# CH32F203VCT6-R1.net
KiCad netlist of a schematic drawn in Altium Designer
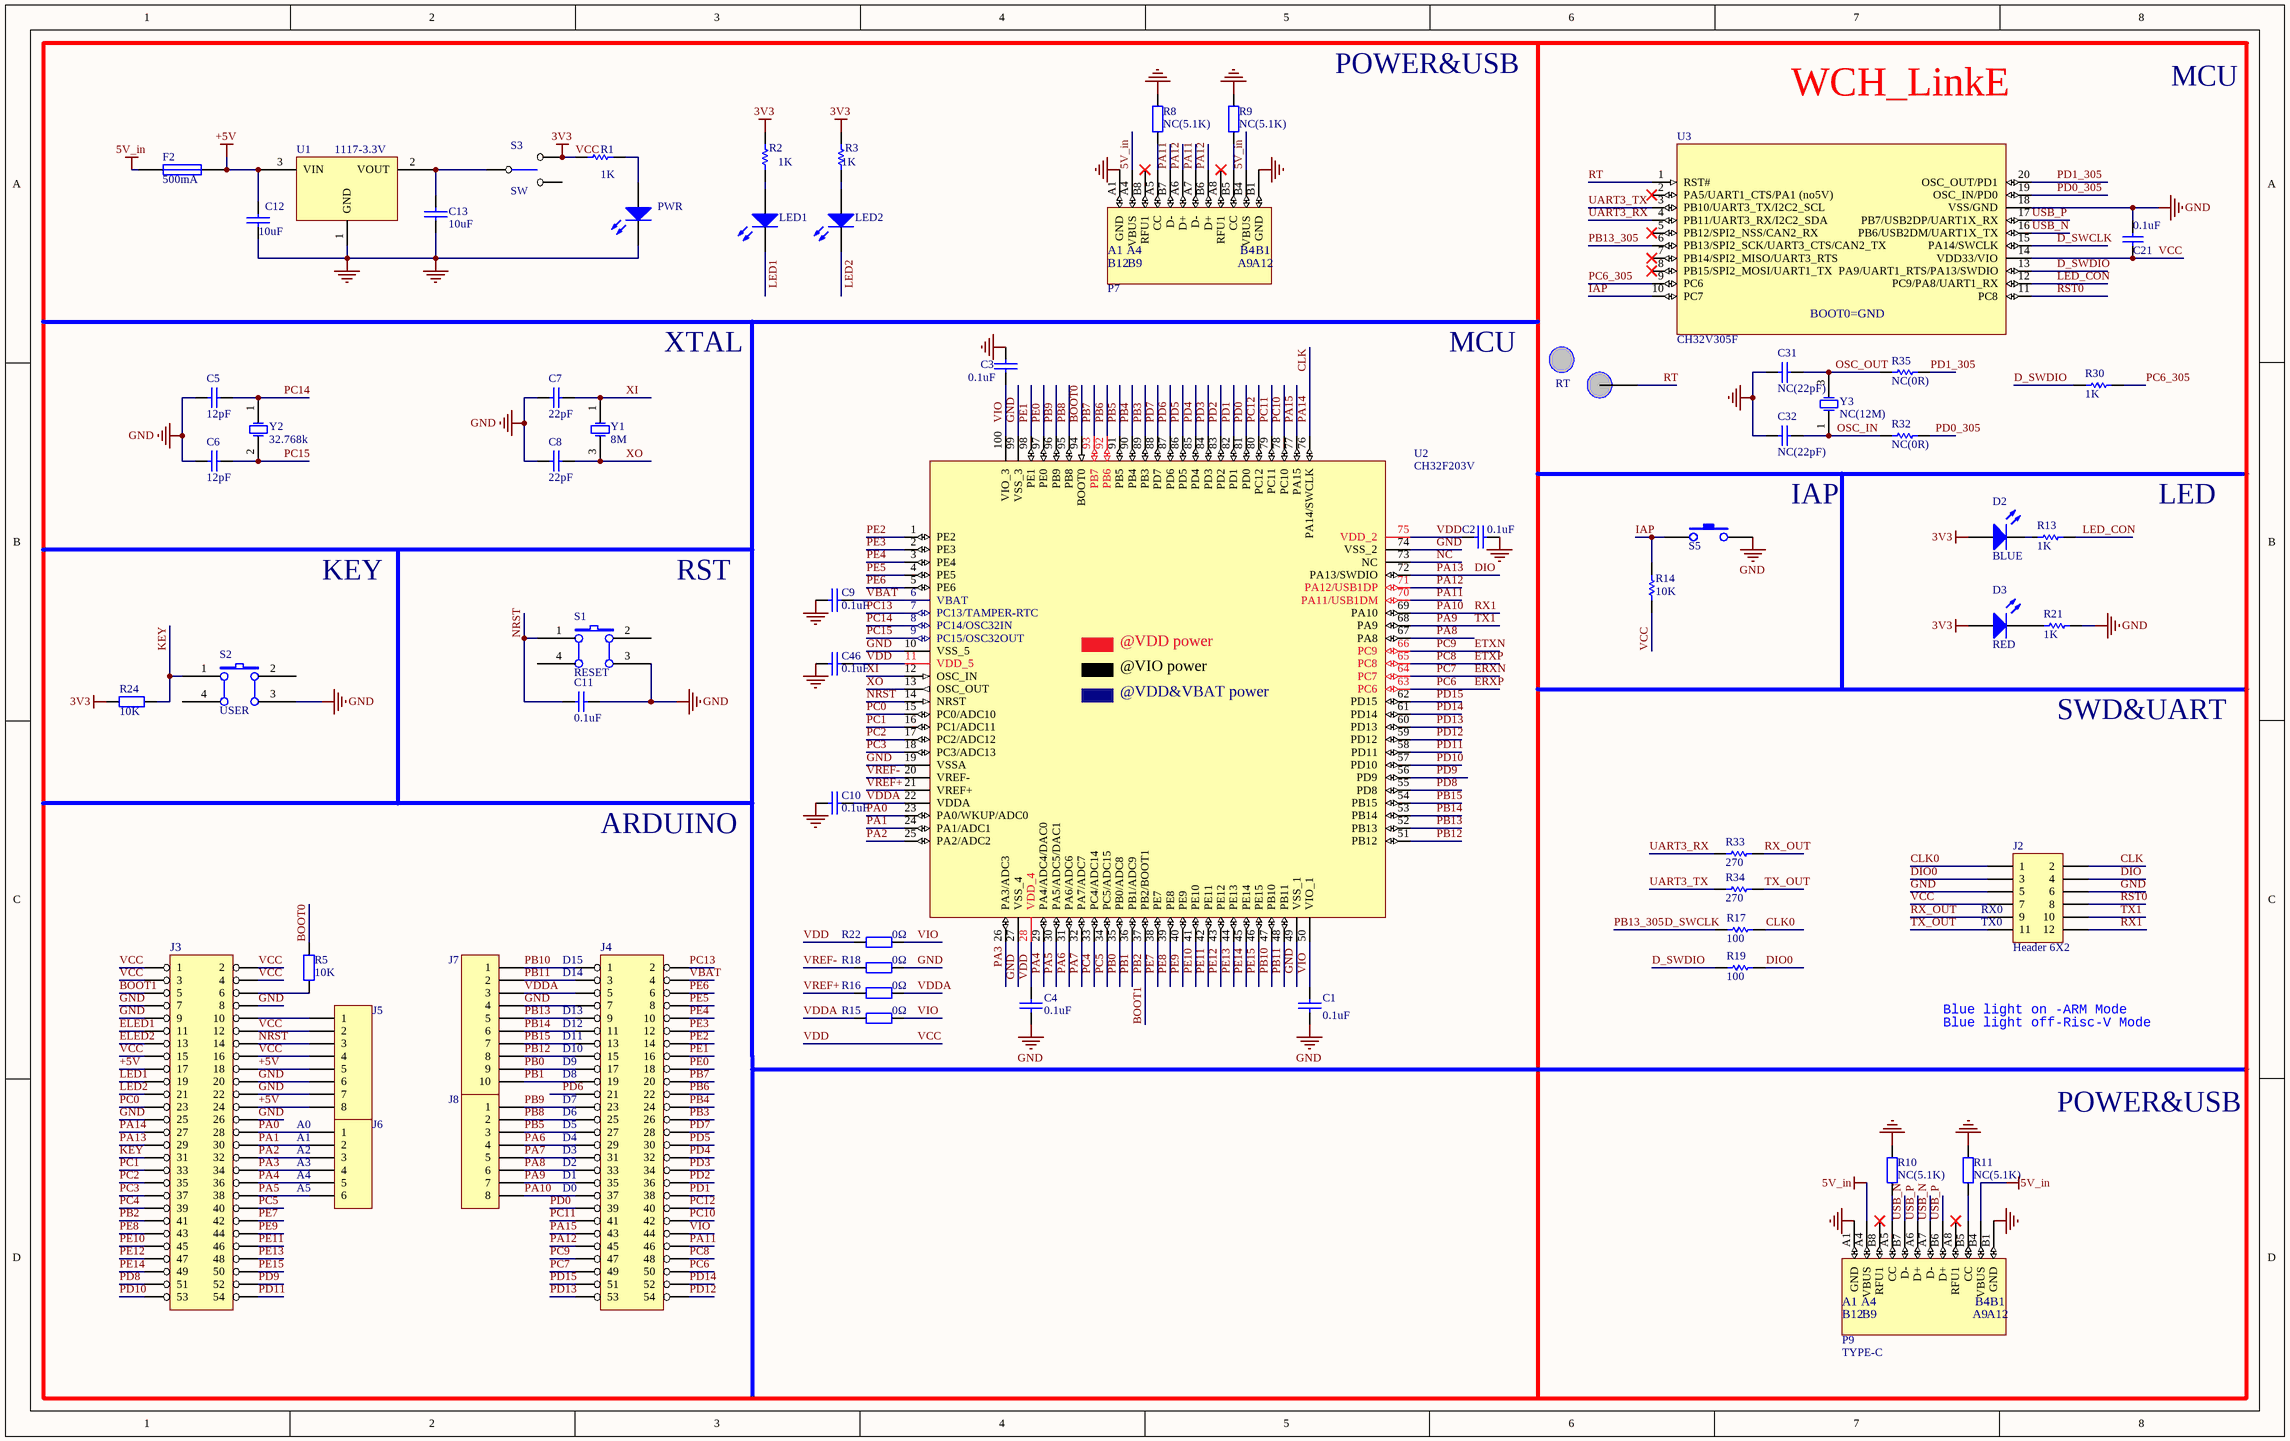
[diagram p0: CH32F203VCT6-R1.SchDoc]

(export (version "E")
  (design (tool "Eeschema 10.0.6"))
  (components
    (comp (ref "C1")
      (value "0.1uF")
      (footprint "0603_C")
      (description "Capacitor")
      (libsource (lib "*") (part "CAP"))
    )
    (comp (ref "C2")
      (value "0.1uF")
      (footprint "0603_C")
      (description "Capacitor")
      (libsource (lib "*") (part "CAP"))
    )
    (comp (ref "C3")
      (value "0.1uF")
      (footprint "0603_C")
      (description "Capacitor")
      (libsource (lib "*") (part "CAP"))
    )
    (comp (ref "C4")
      (value "0.1uF")
      (footprint "0603_C")
      (description "Capacitor")
      (libsource (lib "*") (part "CAP"))
    )
    (comp (ref "C5")
      (value "12pF")
      (footprint "0603_C")
      (description "Capacitor")
      (libsource (lib "Miscellaneous Devices") (part "Cap"))
    )
    (comp (ref "C6")
      (value "12pF")
      (footprint "0603_C")
      (description "Capacitor")
      (libsource (lib "Miscellaneous Devices") (part "Cap"))
    )
    (comp (ref "C7")
      (value "22pF")
      (footprint "0603_C")
      (description "Capacitor")
      (libsource (lib "Miscellaneous Devices") (part "Cap"))
    )
    (comp (ref "C8")
      (value "22pF")
      (footprint "0603_C")
      (description "Capacitor")
      (libsource (lib "Miscellaneous Devices") (part "Cap"))
    )
    (comp (ref "C9")
      (value "0.1uF")
      (footprint "0603_C")
      (description "Capacitor")
      (libsource (lib "*") (part "CAP"))
    )
    (comp (ref "C10")
      (value "0.1uF")
      (footprint "0603_C")
      (description "Capacitor")
      (libsource (lib "*") (part "CAP"))
    )
    (comp (ref "C11")
      (value "0.1uF")
      (footprint "0603_C")
      (description "Capacitor")
      (libsource (lib "Miscellaneous Devices") (part "Cap"))
    )
    (comp (ref "C12")
      (value "10uF")
      (footprint "3216_C")
      (description "Capacitor")
      (libsource (lib "*") (part "CAP"))
    )
    (comp (ref "C13")
      (value "10uF")
      (footprint "3216_C")
      (description "Capacitor")
      (libsource (lib "*") (part "CAP"))
    )
    (comp (ref "C21")
      (value "0.1uF")
      (footprint "0603_C")
      (description "Capacitor")
      (libsource (lib "Miscellaneous Devices") (part "Cap"))
    )
    (comp (ref "C31")
      (value "NC(22pF)")
      (footprint "0603_C")
      (description "Capacitor")
      (fields (field (name "PUBLISHER") "Altium Limited"))
      (libsource (lib "*") (part "Cap"))
    )
    (comp (ref "C32")
      (value "NC(22pF)")
      (footprint "0603_C")
      (description "Capacitor")
      (fields (field (name "PUBLISHER") "Altium Limited"))
      (libsource (lib "*") (part "Cap"))
    )
    (comp (ref "C46")
      (value "0.1uF")
      (footprint "0603_C")
      (description "Capacitor")
      (libsource (lib "*") (part "CAP"))
    )
    (comp (ref "D2")
      (value "BLUE")
      (footprint "0603+")
      (description "Typical RED, GREEN, YELLOW, AMBER GaAs LED")
      (fields (field (name "PUBLISHER") "Altium Limited"))
      (libsource (lib "MYLIB") (part "D0603"))
    )
    (comp (ref "D3")
      (value "RED")
      (footprint "0603+")
      (description "Typical RED, GREEN, YELLOW, AMBER GaAs LED")
      (fields (field (name "PUBLISHER") "Altium Limited"))
      (libsource (lib "MYLIB") (part "D0603"))
    )
    (comp (ref "F2")
      (value "500mA")
      (footprint "0805")
      (description "Fuse")
      (libsource (lib "*") (part "FUSE1"))
    )
    (comp (ref "J2")
      (value "Header 6X2")
      (footprint "IDC12-2.54mm")
      (description "Header, 6-Pin, Dual row")
      (fields (field (name "PUBLISHER") "Altium Limited"))
      (libsource (lib "Miscellaneous Connectors") (part "Header 6X2"))
    )
    (comp (ref "J3")
      (value "HEADER 27x2")
      (footprint "MYPCB:IDC54-2.54MM")
      (description "Header, 27-Pin, Dual row")
      (libsource (lib "wch_sch_others") (part "HEADER 27x2"))
    )
    (comp (ref "J4")
      (value "HEADER 27x2")
      (footprint "MYPCB:IDC54-2.54MM")
      (description "Header, 27-Pin, Dual row")
      (libsource (lib "wch_sch_others") (part "HEADER 27x2"))
    )
    (comp (ref "J5")
      (value "Header 8")
      (footprint "SIP8-2.54mm")
      (description "Header, 8-Pin")
      (fields (field (name "PUBLISHER") "Altium Limited"))
      (libsource (lib "") (part "Header 8_1"))
    )
    (comp (ref "J6")
      (value "Header 6")
      (footprint "SIP6-2.54MM")
      (description "Header, 6-Pin")
      (fields (field (name "PUBLISHER") "Altium Limited"))
      (libsource (lib "Miscellaneous Connectors") (part "Header 6"))
    )
    (comp (ref "J7")
      (value "Header 10")
      (footprint "SIP10-2.54mm")
      (description "Header, 10-Pin")
      (fields (field (name "PUBLISHER") "Altium Limited"))
      (libsource (lib "Miscellaneous Connectors") (part "Header 10"))
    )
    (comp (ref "J8")
      (value "Header 8")
      (footprint "SIP8-2.54mm")
      (description "Header, 8-Pin")
      (fields (field (name "PUBLISHER") "Altium Limited"))
      (libsource (lib "Miscellaneous Connectors") (part "Header 8"))
    )
    (comp (ref "LED1")
      (value "LED1   blue")
      (footprint "0603+")
      (description "Typical INFRARED GaAs LED")
      (fields (field (name "PUBLISHER") "Altium Limited"))
      (libsource (lib "Miscellaneous Devices") (part "LED0"))
    )
    (comp (ref "LED2")
      (value "LED2  blue")
      (footprint "0603+")
      (description "Typical INFRARED GaAs LED")
      (fields (field (name "PUBLISHER") "Altium Limited"))
      (libsource (lib "Miscellaneous Devices") (part "LED0"))
    )
    (comp (ref "P7")
      (value "USBFS")
      (footprint "TYPE-C-Receptacle-2.0")
      (libsource (lib "*") (part "TYPE-C1"))
    )
    (comp (ref "P9")
      (value "TYPE-C")
      (footprint "TYPE-C-Receptacle-2.0")
      (libsource (lib "*") (part "TYPE-C1"))
    )
    (comp (ref "PWR")
      (value "POWER  red")
      (footprint "0603+")
      (description "Typical INFRARED GaAs LED")
      (fields (field (name "PUBLISHER") "Altium Limited"))
      (libsource (lib "Miscellaneous Devices") (part "LED0"))
    )
    (comp (ref "R1")
      (value "1K")
      (footprint "0603")
      (description "Semiconductor Resistor")
      (libsource (lib "Miscellaneous Devices") (part "Res Semi"))
    )
    (comp (ref "R2")
      (value "1K")
      (footprint "0603")
      (description "Semiconductor Resistor")
      (libsource (lib "Miscellaneous Devices") (part "Res Semi"))
    )
    (comp (ref "R3")
      (value "1K")
      (footprint "0603")
      (description "Semiconductor Resistor")
      (libsource (lib "Miscellaneous Devices") (part "Res Semi"))
    )
    (comp (ref "R5")
      (value "10K")
      (footprint "0603")
      (description "Resistor")
      (libsource (lib "Miscellaneous Devices") (part "Res2"))
    )
    (comp (ref "R8")
      (value "NC(5.1K)")
      (footprint "0603")
      (description "Resistor")
      (libsource (lib "") (part "Res2_2"))
    )
    (comp (ref "R9")
      (value "NC(5.1K)")
      (footprint "0603")
      (description "Resistor")
      (libsource (lib "") (part "Res2_2"))
    )
    (comp (ref "R10")
      (value "NC(5.1K)")
      (footprint "0603")
      (description "Resistor")
      (libsource (lib "Miscellaneous Devices") (part "Res2"))
    )
    (comp (ref "R11")
      (value "NC(5.1K)")
      (footprint "0603")
      (description "Resistor")
      (libsource (lib "Miscellaneous Devices") (part "Res2"))
    )
    (comp (ref "R13")
      (value "1K")
      (footprint "0603")
      (description "Resistor")
      (fields (field (name "PUBLISHER") "Altium Limited"))
      (libsource (lib "MYLIB") (part "0603-1"))
    )
    (comp (ref "R14")
      (value "10K")
      (footprint "0603")
      (description "Resistor")
      (fields (field (name "PUBLISHER") "Altium Limited"))
      (libsource (lib "MYLIB") (part "0603-1"))
    )
    (comp (ref "R15")
      (value "0Ω")
      (footprint "0603")
      (description "Resistor")
      (libsource (lib "") (part "Res2_1"))
    )
    (comp (ref "R16")
      (value "0Ω")
      (footprint "0603")
      (description "Resistor")
      (libsource (lib "") (part "Res2_1"))
    )
    (comp (ref "R17")
      (value "100")
      (footprint "0603")
      (description "Resistor")
      (fields (field (name "PUBLISHER") "Altium Limited"))
      (libsource (lib "MYLIB") (part "0603-1"))
    )
    (comp (ref "R18")
      (value "0Ω")
      (footprint "0603")
      (description "Resistor")
      (libsource (lib "") (part "Res2_1"))
    )
    (comp (ref "R19")
      (value "100")
      (footprint "0603")
      (description "Resistor")
      (fields (field (name "PUBLISHER") "Altium Limited"))
      (libsource (lib "MYLIB") (part "0603-1"))
    )
    (comp (ref "R21")
      (value "1K")
      (footprint "0603")
      (description "Resistor")
      (fields (field (name "PUBLISHER") "Altium Limited"))
      (libsource (lib "MYLIB") (part "0603-1"))
    )
    (comp (ref "R22")
      (value "0Ω")
      (footprint "0603")
      (description "Resistor")
      (libsource (lib "") (part "Res2_1"))
    )
    (comp (ref "R24")
      (value "10K")
      (footprint "0603")
      (description "Resistor")
      (libsource (lib "") (part "Res2_1"))
    )
    (comp (ref "R30")
      (value "1K")
      (footprint "0603")
      (description "Resistor")
      (fields (field (name "PUBLISHER") "Altium Limited"))
      (libsource (lib "MYLIB") (part "0603-1"))
    )
    (comp (ref "R32")
      (value "NC(0R)")
      (footprint "0603")
      (description "Resistor")
      (fields (field (name "PUBLISHER") "Altium Limited"))
      (libsource (lib "MYLIB") (part "0603-1"))
    )
    (comp (ref "R33")
      (value "270")
      (footprint "0603")
      (description "Resistor")
      (fields (field (name "PUBLISHER") "Altium Limited"))
      (libsource (lib "MYLIB") (part "0603-1"))
    )
    (comp (ref "R34")
      (value "270")
      (footprint "0603")
      (description "Resistor")
      (fields (field (name "PUBLISHER") "Altium Limited"))
      (libsource (lib "MYLIB") (part "0603-1"))
    )
    (comp (ref "R35")
      (value "NC(0R)")
      (footprint "0603")
      (description "Resistor")
      (fields (field (name "PUBLISHER") "Altium Limited"))
      (libsource (lib "MYLIB") (part "0603-1"))
    )
    (comp (ref "RT")
      (value "Testpoint")
      (footprint "TESTPOINT1")
      (description "测试点")
      (libsource (lib "wch_sch_others") (part "Testpoint"))
    )
    (comp (ref "S1")
      (value "RESET")
      (footprint "KEYX")
      (description "SE PUSHBUTTON")
      (libsource (lib "Documents") (part "SW PUSHBUTTON"))
    )
    (comp (ref "S2")
      (value "USER")
      (footprint "KEYX")
      (description "SE PUSHBUTTON")
      (libsource (lib "Documents") (part "SW PUSHBUTTON"))
    )
    (comp (ref "S3") (value "SW") (footprint "SW1") (libsource (lib "MYSCH") (part "SW")))
    (comp (ref "S5") (value "KEY") (footprint "贴片按键") (libsource (lib "*") (part "KEY")))
    (comp (ref "U1")
      (value "1117-3.3V")
      (footprint "SOT-223")
      (libsource (lib "wch_sch_others") (part "1117-3.3V"))
    )
    (comp (ref "U2")
      (value "CH32F203V")
      (footprint "LQFP100")
      (description "ARM M3 HD-MCU, 144MHz, 8*UART, 10*Timer, 4*OPA")
      (libsource (lib "CHXXX") (part "CH32F203V"))
    )
    (comp (ref "U3")
      (value "CH32V305F")
      (footprint "TSSOP20")
      (description "RISC-V FPU HD-MCU, 144MHz, USB_480M, CAN, UART*2, SPI")
      (libsource (lib "CHXXX") (part "CH32V305F"))
    )
    (comp (ref "Y1")
      (value "8M")
      (footprint "XT3225")
      (description "Crystal Oscillator")
      (fields (field (name "PUBLISHER") "Altium Limited"))
      (libsource (lib "Miscellaneous Devices") (part "XTAL"))
    )
    (comp (ref "Y2")
      (value "32.768k")
      (footprint "FC-135")
      (description "Crystal Oscillator")
      (fields (field (name "PUBLISHER") "Altium Limited"))
      (libsource (lib "") (part "XTAL_1"))
    )
    (comp (ref "Y3")
      (value "NC(12M)")
      (footprint "XT3225")
      (description "Crystal Oscillator")
      (libsource (lib "*") (part "XTAL"))
    )
  )
  (nets
    (net (code "1") (name "+5V") (class "Default")
      (node (ref "C12") (pin "1") (pinfunction "1_1") (pintype "passive"))
      (node (ref "F2") (pin "2") (pinfunction "2_2") (pintype "passive"))
      (node (ref "J3") (pin "17") (pinfunction "17_17") (pintype "passive"))
      (node (ref "J3") (pin "18") (pinfunction "18_18") (pintype "passive"))
      (node (ref "J3") (pin "24") (pinfunction "24_24") (pintype "passive"))
      (node (ref "J5") (pin "5") (pinfunction "5_5") (pintype "passive"))
      (node (ref "J5") (pin "8") (pinfunction "8_8") (pintype "passive"))
      (node (ref "U1") (pin "3") (pinfunction "VIN_3") (pintype "passive"))
    )
    (net (code "2") (name "/BOOT0") (class "Default")
      (node (ref "R5") (pin "2") (pinfunction "2_2") (pintype "passive"))
      (node (ref "U2") (pin "94") (pinfunction "BOOT0_94") (pintype "input"))
    )
    (net (code "3") (name "/BOOT1") (class "Default")
      (node (ref "J3") (pin "41") (pinfunction "41_41") (pintype "passive"))
      (node (ref "J3") (pin "5") (pinfunction "5_5") (pintype "passive"))
      (node (ref "U2") (pin "37") (pinfunction "PB2/BOOT1_37") (pintype "bidirectional"))
    )
    (net (code "4") (name "/CLK") (class "Default")
      (node (ref "J2") (pin "2") (pinfunction "2_2") (pintype "passive"))
      (node (ref "J3") (pin "27") (pinfunction "27_27") (pintype "passive"))
      (node (ref "U2") (pin "76") (pinfunction "PA14/SWCLK_76") (pintype "bidirectional"))
    )
    (net (code "5") (name "/CLK0") (class "Default")
      (node (ref "J2") (pin "1") (pinfunction "1_1") (pintype "passive"))
      (node (ref "R17") (pin "1") (pinfunction "1_1") (pintype "passive"))
    )
    (net (code "6") (name "/DIO") (class "Default")
      (node (ref "J2") (pin "4") (pinfunction "4_4") (pintype "passive"))
      (node (ref "J3") (pin "29") (pinfunction "29_29") (pintype "passive"))
      (node (ref "U2") (pin "72") (pinfunction "PA13/SWDIO_72") (pintype "bidirectional"))
    )
    (net (code "7") (name "/DIO0") (class "Default")
      (node (ref "J2") (pin "3") (pinfunction "3_3") (pintype "passive"))
      (node (ref "R19") (pin "1") (pinfunction "1_1") (pintype "passive"))
    )
    (net (code "8") (name "/D_SWCLK") (class "Default")
      (node (ref "R17") (pin "2") (pinfunction "2_2") (pintype "passive"))
      (node (ref "U3") (pin "15") (pinfunction "PA14/SWCLK_15") (pintype "bidirectional"))
      (node (ref "U3") (pin "6") (pinfunction "PB13/SPI2_SCK/UART3_CTS/CAN2_TX_6") (pintype "bidirectional"))
    )
    (net (code "9") (name "/D_SWDIO") (class "Default")
      (node (ref "R19") (pin "2") (pinfunction "2_2") (pintype "passive"))
      (node (ref "R30") (pin "1") (pinfunction "1_1") (pintype "passive"))
      (node (ref "U3") (pin "13") (pinfunction "PA9/UART1_RTS/PA13/SWDIO_13") (pintype "bidirectional"))
    )
    (net (code "10") (name "/ELED1") (class "Default")
      (node (ref "J3") (pin "11") (pinfunction "11_11") (pintype "passive"))
    )
    (net (code "11") (name "/ELED2") (class "Default")
      (node (ref "J3") (pin "13") (pinfunction "13_13") (pintype "passive"))
    )
    (net (code "12") (name "/ERXN") (class "Default")
      (node (ref "J4") (pin "49") (pinfunction "49_49") (pintype "passive"))
      (node (ref "U2") (pin "64") (pinfunction "PC7_64") (pintype "bidirectional"))
    )
    (net (code "13") (name "/ERXP") (class "Default")
      (node (ref "J4") (pin "50") (pinfunction "50_50") (pintype "passive"))
      (node (ref "U2") (pin "63") (pinfunction "PC6_63") (pintype "bidirectional"))
    )
    (net (code "14") (name "/ETXN") (class "Default")
      (node (ref "J4") (pin "47") (pinfunction "47_47") (pintype "passive"))
      (node (ref "U2") (pin "66") (pinfunction "PC9_66") (pintype "bidirectional"))
    )
    (net (code "15") (name "/ETXP") (class "Default")
      (node (ref "J4") (pin "48") (pinfunction "48_48") (pintype "passive"))
      (node (ref "U2") (pin "65") (pinfunction "PC8_65") (pintype "bidirectional"))
    )
    (net (code "16") (name "/IAP") (class "Default")
      (node (ref "R14") (pin "1") (pinfunction "1_1") (pintype "passive"))
      (node (ref "S5") (pin "1") (pinfunction "1_1") (pintype "passive"))
      (node (ref "U3") (pin "10") (pinfunction "PC7_10") (pintype "bidirectional"))
    )
    (net (code "17") (name "/KEY") (class "Default")
      (node (ref "J3") (pin "31") (pinfunction "31_31") (pintype "passive"))
      (node (ref "R24") (pin "1") (pinfunction "1_1") (pintype "passive"))
      (node (ref "S2") (pin "1") (pinfunction "A0_1") (pintype "passive"))
    )
    (net (code "18") (name "/LED1") (class "Default")
      (node (ref "J3") (pin "19") (pinfunction "19_19") (pintype "passive"))
      (node (ref "LED1") (pin "2") (pinfunction "K_2") (pintype "passive"))
    )
    (net (code "19") (name "/LED2") (class "Default")
      (node (ref "J3") (pin "21") (pinfunction "21_21") (pintype "passive"))
      (node (ref "LED2") (pin "2") (pinfunction "K_2") (pintype "passive"))
    )
    (net (code "20") (name "/LED_CON") (class "Default")
      (node (ref "R13") (pin "1") (pinfunction "1_1") (pintype "passive"))
      (node (ref "U3") (pin "12") (pinfunction "PC9/PA8/UART1_RX_12") (pintype "bidirectional"))
    )
    (net (code "21") (name "/NC") (class "Default")
      (node (ref "U2") (pin "73") (pinfunction "NC_73") (pintype "tri_state"))
    )
    (net (code "22") (name "/NRST") (class "Default")
      (node (ref "C11") (pin "2") (pinfunction "2_2") (pintype "passive"))
      (node (ref "J3") (pin "14") (pinfunction "14_14") (pintype "passive"))
      (node (ref "J5") (pin "3") (pinfunction "3_3") (pintype "passive"))
      (node (ref "S1") (pin "1") (pinfunction "A0_1") (pintype "passive"))
      (node (ref "U2") (pin "14") (pinfunction "NRST_14") (pintype "input"))
    )
    (net (code "23") (name "/OSC_IN") (class "Default")
      (node (ref "C32") (pin "2") (pinfunction "2_2") (pintype "passive"))
      (node (ref "R32") (pin "2") (pinfunction "2_2") (pintype "passive"))
      (node (ref "Y3") (pin "1") (pinfunction "OSC1_1") (pintype "passive"))
    )
    (net (code "24") (name "/OSC_OUT") (class "Default")
      (node (ref "C31") (pin "2") (pinfunction "2_2") (pintype "passive"))
      (node (ref "R35") (pin "2") (pinfunction "2_2") (pintype "passive"))
      (node (ref "Y3") (pin "3") (pinfunction "OSC2_3") (pintype "passive"))
    )
    (net (code "25") (name "/PA0") (class "Default")
      (node (ref "J3") (pin "28") (pinfunction "28_28") (pintype "passive"))
      (node (ref "J6") (pin "1") (pinfunction "1_1") (pintype "passive"))
      (node (ref "U2") (pin "23") (pinfunction "PA0/WKUP/ADC0_23") (pintype "bidirectional"))
    )
    (net (code "26") (name "/PA1") (class "Default")
      (node (ref "J3") (pin "30") (pinfunction "30_30") (pintype "passive"))
      (node (ref "J6") (pin "2") (pinfunction "2_2") (pintype "passive"))
      (node (ref "U2") (pin "24") (pinfunction "PA1/ADC1_24") (pintype "bidirectional"))
    )
    (net (code "27") (name "/PA2") (class "Default")
      (node (ref "J3") (pin "32") (pinfunction "32_32") (pintype "passive"))
      (node (ref "J6") (pin "3") (pinfunction "3_3") (pintype "passive"))
      (node (ref "U2") (pin "25") (pinfunction "PA2/ADC2_25") (pintype "bidirectional"))
    )
    (net (code "28") (name "/PA3") (class "Default")
      (node (ref "J3") (pin "34") (pinfunction "34_34") (pintype "passive"))
      (node (ref "J6") (pin "4") (pinfunction "4_4") (pintype "passive"))
      (node (ref "U2") (pin "26") (pinfunction "PA3/ADC3_26") (pintype "bidirectional"))
    )
    (net (code "29") (name "/PA4") (class "Default")
      (node (ref "J3") (pin "36") (pinfunction "36_36") (pintype "passive"))
      (node (ref "J6") (pin "5") (pinfunction "5_5") (pintype "passive"))
      (node (ref "U2") (pin "29") (pinfunction "PA4/ADC4/DAC0_29") (pintype "bidirectional"))
    )
    (net (code "30") (name "/PA5") (class "Default")
      (node (ref "J3") (pin "38") (pinfunction "38_38") (pintype "passive"))
      (node (ref "J6") (pin "6") (pinfunction "6_6") (pintype "passive"))
      (node (ref "U2") (pin "30") (pinfunction "PA5/ADC5/DAC1_30") (pintype "bidirectional"))
    )
    (net (code "31") (name "/PA6") (class "Default")
      (node (ref "J4") (pin "29") (pinfunction "29_29") (pintype "passive"))
      (node (ref "J8") (pin "4") (pinfunction "4_4") (pintype "passive"))
      (node (ref "U2") (pin "31") (pinfunction "PA6/ADC6_31") (pintype "bidirectional"))
    )
    (net (code "32") (name "/PA7") (class "Default")
      (node (ref "J4") (pin "31") (pinfunction "31_31") (pintype "passive"))
      (node (ref "J8") (pin "5") (pinfunction "5_5") (pintype "passive"))
      (node (ref "U2") (pin "32") (pinfunction "PA7/ADC7_32") (pintype "bidirectional"))
    )
    (net (code "33") (name "/PA8") (class "Default")
      (node (ref "J4") (pin "33") (pinfunction "33_33") (pintype "passive"))
      (node (ref "J8") (pin "6") (pinfunction "6_6") (pintype "passive"))
      (node (ref "U2") (pin "67") (pinfunction "PA8_67") (pintype "bidirectional"))
    )
    (net (code "34") (name "/PA9") (class "Default")
      (node (ref "J2") (pin "10") (pinfunction "10_10") (pintype "passive"))
      (node (ref "J4") (pin "35") (pinfunction "35_35") (pintype "passive"))
      (node (ref "J8") (pin "7") (pinfunction "7_7") (pintype "passive"))
      (node (ref "U2") (pin "68") (pinfunction "PA9_68") (pintype "bidirectional"))
    )
    (net (code "35") (name "/PA10") (class "Default")
      (node (ref "J2") (pin "12") (pinfunction "12_12") (pintype "passive"))
      (node (ref "J4") (pin "37") (pinfunction "37_37") (pintype "passive"))
      (node (ref "J8") (pin "8") (pinfunction "8_8") (pintype "passive"))
      (node (ref "U2") (pin "69") (pinfunction "PA10_69") (pintype "bidirectional"))
    )
    (net (code "36") (name "/PA11") (class "Default")
      (node (ref "J4") (pin "46") (pinfunction "46_46") (pintype "passive"))
      (node (ref "P7") (pin "A7") (pinfunction "D-_A7") (pintype "bidirectional"))
      (node (ref "P7") (pin "B7") (pinfunction "D-_B7") (pintype "bidirectional"))
      (node (ref "U2") (pin "70") (pinfunction "PA11/USB1DM_70") (pintype "bidirectional"))
    )
    (net (code "37") (name "/PA12") (class "Default")
      (node (ref "J4") (pin "45") (pinfunction "45_45") (pintype "passive"))
      (node (ref "P7") (pin "A6") (pinfunction "D+_A6") (pintype "bidirectional"))
      (node (ref "P7") (pin "B6") (pinfunction "D+_B6") (pintype "bidirectional"))
      (node (ref "U2") (pin "71") (pinfunction "PA12/USB1DP_71") (pintype "bidirectional"))
    )
    (net (code "38") (name "/PA15") (class "Default")
      (node (ref "J4") (pin "43") (pinfunction "43_43") (pintype "passive"))
      (node (ref "U2") (pin "77") (pinfunction "PA15_77") (pintype "bidirectional"))
    )
    (net (code "39") (name "/PB0") (class "Default")
      (node (ref "J4") (pin "17") (pinfunction "17_17") (pintype "passive"))
      (node (ref "J7") (pin "9") (pinfunction "9_9") (pintype "passive"))
      (node (ref "U2") (pin "35") (pinfunction "PB0/ADC8_35") (pintype "bidirectional"))
    )
    (net (code "40") (name "/PB1") (class "Default")
      (node (ref "J4") (pin "19") (pinfunction "19_19") (pintype "passive"))
      (node (ref "J7") (pin "10") (pinfunction "10_10") (pintype "passive"))
      (node (ref "U2") (pin "36") (pinfunction "PB1/ADC9_36") (pintype "bidirectional"))
    )
    (net (code "41") (name "/PB3") (class "Default")
      (node (ref "J4") (pin "26") (pinfunction "26_26") (pintype "passive"))
      (node (ref "U2") (pin "89") (pinfunction "PB3_89") (pintype "bidirectional"))
    )
    (net (code "42") (name "/PB4") (class "Default")
      (node (ref "J4") (pin "24") (pinfunction "24_24") (pintype "passive"))
      (node (ref "U2") (pin "90") (pinfunction "PB4_90") (pintype "bidirectional"))
    )
    (net (code "43") (name "/PB5") (class "Default")
      (node (ref "J4") (pin "27") (pinfunction "27_27") (pintype "passive"))
      (node (ref "J8") (pin "3") (pinfunction "3_3") (pintype "passive"))
      (node (ref "U2") (pin "91") (pinfunction "PB5_91") (pintype "bidirectional"))
    )
    (net (code "44") (name "/PB6") (class "Default")
      (node (ref "J4") (pin "22") (pinfunction "22_22") (pintype "passive"))
      (node (ref "U2") (pin "92") (pinfunction "PB6_92") (pintype "bidirectional"))
    )
    (net (code "45") (name "/PB7") (class "Default")
      (node (ref "J4") (pin "20") (pinfunction "20_20") (pintype "passive"))
      (node (ref "U2") (pin "93") (pinfunction "PB7_93") (pintype "bidirectional"))
    )
    (net (code "46") (name "/PB8") (class "Default")
      (node (ref "J4") (pin "25") (pinfunction "25_25") (pintype "passive"))
      (node (ref "J8") (pin "2") (pinfunction "2_2") (pintype "passive"))
      (node (ref "U2") (pin "95") (pinfunction "PB8_95") (pintype "bidirectional"))
    )
    (net (code "47") (name "/PB9") (class "Default")
      (node (ref "J4") (pin "23") (pinfunction "23_23") (pintype "passive"))
      (node (ref "J8") (pin "1") (pinfunction "1_1") (pintype "passive"))
      (node (ref "U2") (pin "96") (pinfunction "PB9_96") (pintype "bidirectional"))
    )
    (net (code "48") (name "/PB10") (class "Default")
      (node (ref "J4") (pin "1") (pinfunction "1_1") (pintype "passive"))
      (node (ref "J7") (pin "1") (pinfunction "1_1") (pintype "passive"))
      (node (ref "U2") (pin "47") (pinfunction "PB10_47") (pintype "bidirectional"))
    )
    (net (code "49") (name "/PB11") (class "Default")
      (node (ref "J4") (pin "3") (pinfunction "3_3") (pintype "passive"))
      (node (ref "J7") (pin "2") (pinfunction "2_2") (pintype "passive"))
      (node (ref "U2") (pin "48") (pinfunction "PB11_48") (pintype "bidirectional"))
    )
    (net (code "50") (name "/PB12") (class "Default")
      (node (ref "J4") (pin "15") (pinfunction "15_15") (pintype "passive"))
      (node (ref "J7") (pin "8") (pinfunction "8_8") (pintype "passive"))
      (node (ref "U2") (pin "51") (pinfunction "PB12_51") (pintype "bidirectional"))
    )
    (net (code "51") (name "/PB13") (class "Default")
      (node (ref "J4") (pin "9") (pinfunction "9_9") (pintype "passive"))
      (node (ref "J7") (pin "5") (pinfunction "5_5") (pintype "passive"))
      (node (ref "U2") (pin "52") (pinfunction "PB13_52") (pintype "bidirectional"))
    )
    (net (code "52") (name "/PB14") (class "Default")
      (node (ref "J4") (pin "11") (pinfunction "11_11") (pintype "passive"))
      (node (ref "J7") (pin "6") (pinfunction "6_6") (pintype "passive"))
      (node (ref "U2") (pin "53") (pinfunction "PB14_53") (pintype "bidirectional"))
    )
    (net (code "53") (name "/PB15") (class "Default")
      (node (ref "J4") (pin "13") (pinfunction "13_13") (pintype "passive"))
      (node (ref "J7") (pin "7") (pinfunction "7_7") (pintype "passive"))
      (node (ref "U2") (pin "54") (pinfunction "PB15_54") (pintype "bidirectional"))
    )
    (net (code "54") (name "/PC0") (class "Default")
      (node (ref "J3") (pin "23") (pinfunction "23_23") (pintype "passive"))
      (node (ref "U2") (pin "15") (pinfunction "PC0/ADC10_15") (pintype "bidirectional"))
    )
    (net (code "55") (name "/PC1") (class "Default")
      (node (ref "J3") (pin "33") (pinfunction "33_33") (pintype "passive"))
      (node (ref "U2") (pin "16") (pinfunction "PC1/ADC11_16") (pintype "bidirectional"))
    )
    (net (code "56") (name "/PC2") (class "Default")
      (node (ref "J3") (pin "35") (pinfunction "35_35") (pintype "passive"))
      (node (ref "U2") (pin "17") (pinfunction "PC2/ADC12_17") (pintype "bidirectional"))
    )
    (net (code "57") (name "/PC3") (class "Default")
      (node (ref "J3") (pin "37") (pinfunction "37_37") (pintype "passive"))
      (node (ref "U2") (pin "18") (pinfunction "PC3/ADC13_18") (pintype "bidirectional"))
    )
    (net (code "58") (name "/PC4") (class "Default")
      (node (ref "J3") (pin "39") (pinfunction "39_39") (pintype "passive"))
      (node (ref "U2") (pin "33") (pinfunction "PC4/ADC14_33") (pintype "bidirectional"))
    )
    (net (code "59") (name "/PC5") (class "Default")
      (node (ref "J3") (pin "40") (pinfunction "40_40") (pintype "passive"))
      (node (ref "U2") (pin "34") (pinfunction "PC5/ADC15_34") (pintype "bidirectional"))
    )
    (net (code "60") (name "/PC6_305") (class "Default")
      (node (ref "R30") (pin "2") (pinfunction "2_2") (pintype "passive"))
      (node (ref "U3") (pin "9") (pinfunction "PC6_9") (pintype "bidirectional"))
    )
    (net (code "61") (name "/PC10") (class "Default")
      (node (ref "J4") (pin "42") (pinfunction "42_42") (pintype "passive"))
      (node (ref "U2") (pin "78") (pinfunction "PC10_78") (pintype "bidirectional"))
    )
    (net (code "62") (name "/PC11") (class "Default")
      (node (ref "J4") (pin "41") (pinfunction "41_41") (pintype "passive"))
      (node (ref "U2") (pin "79") (pinfunction "PC11_79") (pintype "bidirectional"))
    )
    (net (code "63") (name "/PC12") (class "Default")
      (node (ref "J4") (pin "40") (pinfunction "40_40") (pintype "passive"))
      (node (ref "U2") (pin "80") (pinfunction "PC12_80") (pintype "bidirectional"))
    )
    (net (code "64") (name "/PC13") (class "Default")
      (node (ref "J4") (pin "2") (pinfunction "2_2") (pintype "passive"))
      (node (ref "U2") (pin "7") (pinfunction "PC13/TAMPER-RTC_7") (pintype "bidirectional"))
    )
    (net (code "65") (name "/PC14") (class "Default")
      (node (ref "C5") (pin "1") (pinfunction "1_1") (pintype "passive"))
      (node (ref "U2") (pin "8") (pinfunction "PC14/OSC32IN_8") (pintype "bidirectional"))
      (node (ref "Y2") (pin "1") (pinfunction "OSC1_1") (pintype "passive"))
    )
    (net (code "66") (name "/PC15") (class "Default")
      (node (ref "C6") (pin "1") (pinfunction "1_1") (pintype "passive"))
      (node (ref "U2") (pin "9") (pinfunction "PC15/OSC32OUT_9") (pintype "bidirectional"))
      (node (ref "Y2") (pin "2") (pinfunction "OSC2_2") (pintype "passive"))
    )
    (net (code "67") (name "/PD0") (class "Default")
      (node (ref "J4") (pin "39") (pinfunction "39_39") (pintype "passive"))
      (node (ref "U2") (pin "81") (pinfunction "PD0_81") (pintype "bidirectional"))
    )
    (net (code "68") (name "/PD0_305") (class "Default")
      (node (ref "R32") (pin "1") (pinfunction "1_1") (pintype "passive"))
      (node (ref "U3") (pin "19") (pinfunction "OSC_IN/PD0_19") (pintype "bidirectional"))
    )
    (net (code "69") (name "/PD1") (class "Default")
      (node (ref "J4") (pin "38") (pinfunction "38_38") (pintype "passive"))
      (node (ref "U2") (pin "82") (pinfunction "PD1_82") (pintype "bidirectional"))
    )
    (net (code "70") (name "/PD1_305") (class "Default")
      (node (ref "R35") (pin "1") (pinfunction "1_1") (pintype "passive"))
      (node (ref "U3") (pin "20") (pinfunction "OSC_OUT/PD1_20") (pintype "bidirectional"))
    )
    (net (code "71") (name "/PD2") (class "Default")
      (node (ref "J4") (pin "36") (pinfunction "36_36") (pintype "passive"))
      (node (ref "U2") (pin "83") (pinfunction "PD2_83") (pintype "bidirectional"))
    )
    (net (code "72") (name "/PD3") (class "Default")
      (node (ref "J4") (pin "34") (pinfunction "34_34") (pintype "passive"))
      (node (ref "U2") (pin "84") (pinfunction "PD3_84") (pintype "bidirectional"))
    )
    (net (code "73") (name "/PD4") (class "Default")
      (node (ref "J4") (pin "32") (pinfunction "32_32") (pintype "passive"))
      (node (ref "U2") (pin "85") (pinfunction "PD4_85") (pintype "bidirectional"))
    )
    (net (code "74") (name "/PD5") (class "Default")
      (node (ref "J4") (pin "30") (pinfunction "30_30") (pintype "passive"))
      (node (ref "U2") (pin "86") (pinfunction "PD5_86") (pintype "bidirectional"))
    )
    (net (code "75") (name "/PD6") (class "Default")
      (node (ref "J4") (pin "21") (pinfunction "21_21") (pintype "passive"))
      (node (ref "U2") (pin "87") (pinfunction "PD6_87") (pintype "bidirectional"))
    )
    (net (code "76") (name "/PD7") (class "Default")
      (node (ref "J4") (pin "28") (pinfunction "28_28") (pintype "passive"))
      (node (ref "U2") (pin "88") (pinfunction "PD7_88") (pintype "bidirectional"))
    )
    (net (code "77") (name "/PD8") (class "Default")
      (node (ref "J3") (pin "51") (pinfunction "51_51") (pintype "passive"))
      (node (ref "U2") (pin "55") (pinfunction "PD8_55") (pintype "bidirectional"))
    )
    (net (code "78") (name "/PD9") (class "Default")
      (node (ref "J3") (pin "52") (pinfunction "52_52") (pintype "passive"))
      (node (ref "U2") (pin "56") (pinfunction "PD9_56") (pintype "bidirectional"))
    )
    (net (code "79") (name "/PD10") (class "Default")
      (node (ref "J3") (pin "53") (pinfunction "53_53") (pintype "passive"))
      (node (ref "U2") (pin "57") (pinfunction "PD10_57") (pintype "bidirectional"))
    )
    (net (code "80") (name "/PD11") (class "Default")
      (node (ref "J3") (pin "54") (pinfunction "54_54") (pintype "passive"))
      (node (ref "U2") (pin "58") (pinfunction "PD11_58") (pintype "bidirectional"))
    )
    (net (code "81") (name "/PD12") (class "Default")
      (node (ref "J4") (pin "54") (pinfunction "54_54") (pintype "passive"))
      (node (ref "U2") (pin "59") (pinfunction "PD12_59") (pintype "bidirectional"))
    )
    (net (code "82") (name "/PD13") (class "Default")
      (node (ref "J4") (pin "53") (pinfunction "53_53") (pintype "passive"))
      (node (ref "U2") (pin "60") (pinfunction "PD13_60") (pintype "bidirectional"))
    )
    (net (code "83") (name "/PD14") (class "Default")
      (node (ref "J4") (pin "52") (pinfunction "52_52") (pintype "passive"))
      (node (ref "U2") (pin "61") (pinfunction "PD14_61") (pintype "bidirectional"))
    )
    (net (code "84") (name "/PD15") (class "Default")
      (node (ref "J4") (pin "51") (pinfunction "51_51") (pintype "passive"))
      (node (ref "U2") (pin "62") (pinfunction "PD15_62") (pintype "bidirectional"))
    )
    (net (code "85") (name "/PE0") (class "Default")
      (node (ref "J4") (pin "18") (pinfunction "18_18") (pintype "passive"))
      (node (ref "U2") (pin "97") (pinfunction "PE0_97") (pintype "bidirectional"))
    )
    (net (code "86") (name "/PE1") (class "Default")
      (node (ref "J4") (pin "16") (pinfunction "16_16") (pintype "passive"))
      (node (ref "U2") (pin "98") (pinfunction "PE1_98") (pintype "bidirectional"))
    )
    (net (code "87") (name "/PE2") (class "Default")
      (node (ref "J4") (pin "14") (pinfunction "14_14") (pintype "passive"))
      (node (ref "U2") (pin "1") (pinfunction "PE2_1") (pintype "bidirectional"))
    )
    (net (code "88") (name "/PE3") (class "Default")
      (node (ref "J4") (pin "12") (pinfunction "12_12") (pintype "passive"))
      (node (ref "U2") (pin "2") (pinfunction "PE3_2") (pintype "bidirectional"))
    )
    (net (code "89") (name "/PE4") (class "Default")
      (node (ref "J4") (pin "10") (pinfunction "10_10") (pintype "passive"))
      (node (ref "U2") (pin "3") (pinfunction "PE4_3") (pintype "bidirectional"))
    )
    (net (code "90") (name "/PE5") (class "Default")
      (node (ref "J4") (pin "8") (pinfunction "8_8") (pintype "passive"))
      (node (ref "U2") (pin "4") (pinfunction "PE5_4") (pintype "bidirectional"))
    )
    (net (code "91") (name "/PE6") (class "Default")
      (node (ref "J4") (pin "6") (pinfunction "6_6") (pintype "passive"))
      (node (ref "U2") (pin "5") (pinfunction "PE6_5") (pintype "bidirectional"))
    )
    (net (code "92") (name "/PE7") (class "Default")
      (node (ref "J3") (pin "42") (pinfunction "42_42") (pintype "passive"))
      (node (ref "U2") (pin "38") (pinfunction "PE7_38") (pintype "bidirectional"))
    )
    (net (code "93") (name "/PE8") (class "Default")
      (node (ref "J3") (pin "43") (pinfunction "43_43") (pintype "passive"))
      (node (ref "U2") (pin "39") (pinfunction "PE8_39") (pintype "bidirectional"))
    )
    (net (code "94") (name "/PE9") (class "Default")
      (node (ref "J3") (pin "44") (pinfunction "44_44") (pintype "passive"))
      (node (ref "U2") (pin "40") (pinfunction "PE9_40") (pintype "bidirectional"))
    )
    (net (code "95") (name "/PE10") (class "Default")
      (node (ref "J3") (pin "45") (pinfunction "45_45") (pintype "passive"))
      (node (ref "U2") (pin "41") (pinfunction "PE10_41") (pintype "bidirectional"))
    )
    (net (code "96") (name "/PE11") (class "Default")
      (node (ref "J3") (pin "46") (pinfunction "46_46") (pintype "passive"))
      (node (ref "U2") (pin "42") (pinfunction "PE11_42") (pintype "bidirectional"))
    )
    (net (code "97") (name "/PE12") (class "Default")
      (node (ref "J3") (pin "47") (pinfunction "47_47") (pintype "passive"))
      (node (ref "U2") (pin "43") (pinfunction "PE12_43") (pintype "bidirectional"))
    )
    (net (code "98") (name "/PE13") (class "Default")
      (node (ref "J3") (pin "48") (pinfunction "48_48") (pintype "passive"))
      (node (ref "U2") (pin "44") (pinfunction "PE13_44") (pintype "bidirectional"))
    )
    (net (code "99") (name "/PE14") (class "Default")
      (node (ref "J3") (pin "49") (pinfunction "49_49") (pintype "passive"))
      (node (ref "U2") (pin "45") (pinfunction "PE14_45") (pintype "bidirectional"))
    )
    (net (code "100") (name "/PE15") (class "Default")
      (node (ref "J3") (pin "50") (pinfunction "50_50") (pintype "passive"))
      (node (ref "U2") (pin "46") (pinfunction "PE15_46") (pintype "bidirectional"))
    )
    (net (code "101") (name "/RST0") (class "Default")
      (node (ref "J2") (pin "8") (pinfunction "8_8") (pintype "passive"))
      (node (ref "U3") (pin "11") (pinfunction "PC8_11") (pintype "bidirectional"))
    )
    (net (code "102") (name "/RT") (class "Default")
      (node (ref "RT") (pin "1") (pinfunction "point_1") (pintype "passive"))
      (node (ref "U3") (pin "1") (pinfunction "RST#_1") (pintype "input"))
    )
    (net (code "103") (name "/RX_OUT") (class "Default")
      (node (ref "J2") (pin "9") (pinfunction "9_9") (pintype "passive"))
      (node (ref "R33") (pin "1") (pinfunction "1_1") (pintype "passive"))
    )
    (net (code "104") (name "/TX_OUT") (class "Default")
      (node (ref "J2") (pin "11") (pinfunction "11_11") (pintype "passive"))
      (node (ref "R34") (pin "1") (pinfunction "1_1") (pintype "passive"))
    )
    (net (code "105") (name "/UART3_RX") (class "Default")
      (node (ref "R33") (pin "2") (pinfunction "2_2") (pintype "passive"))
      (node (ref "U3") (pin "4") (pinfunction "PB11/UART3_RX/I2C2_SDA_4") (pintype "bidirectional"))
    )
    (net (code "106") (name "/UART3_TX") (class "Default")
      (node (ref "R34") (pin "2") (pinfunction "2_2") (pintype "passive"))
      (node (ref "U3") (pin "3") (pinfunction "PB10/UART3_TX/I2C2_SCL_3") (pintype "bidirectional"))
    )
    (net (code "107") (name "/USB_N") (class "Default")
      (node (ref "P9") (pin "A7") (pinfunction "D-_A7") (pintype "bidirectional"))
      (node (ref "P9") (pin "B7") (pinfunction "D-_B7") (pintype "bidirectional"))
      (node (ref "U3") (pin "16") (pinfunction "PB6/USB2DM/UART1X_TX_16") (pintype "bidirectional"))
    )
    (net (code "108") (name "/USB_P") (class "Default")
      (node (ref "P9") (pin "A6") (pinfunction "D+_A6") (pintype "bidirectional"))
      (node (ref "P9") (pin "B6") (pinfunction "D+_B6") (pintype "bidirectional"))
      (node (ref "U3") (pin "17") (pinfunction "PB7/USB2DP/UART1X_RX_17") (pintype "bidirectional"))
    )
    (net (code "109") (name "/VBAT") (class "Default")
      (node (ref "C9") (pin "2") (pinfunction "2_2") (pintype "passive"))
      (node (ref "J4") (pin "4") (pinfunction "4_4") (pintype "passive"))
      (node (ref "U2") (pin "6") (pinfunction "VBAT_6") (pintype "power_in"))
    )
    (net (code "110") (name "/VDDA") (class "Default")
      (node (ref "C10") (pin "2") (pinfunction "2_2") (pintype "passive"))
      (node (ref "J4") (pin "5") (pinfunction "5_5") (pintype "passive"))
      (node (ref "J7") (pin "3") (pinfunction "3_3") (pintype "passive"))
      (node (ref "R15") (pin "2") (pinfunction "2_2") (pintype "passive"))
      (node (ref "R16") (pin "1") (pinfunction "1_1") (pintype "passive"))
      (node (ref "U2") (pin "22") (pinfunction "VDDA_22") (pintype "power_in"))
    )
    (net (code "111") (name "/VIO") (class "Default")
      (node (ref "C1") (pin "2") (pinfunction "2_2") (pintype "passive"))
      (node (ref "C3") (pin "1") (pinfunction "1_1") (pintype "passive"))
      (node (ref "J4") (pin "44") (pinfunction "44_44") (pintype "passive"))
      (node (ref "R15") (pin "1") (pinfunction "1_1") (pintype "passive"))
      (node (ref "R22") (pin "1") (pinfunction "1_1") (pintype "passive"))
      (node (ref "U2") (pin "100") (pinfunction "VIO_3_100") (pintype "power_in"))
      (node (ref "U2") (pin "50") (pinfunction "VIO_1_50") (pintype "power_in"))
    )
    (net (code "112") (name "/VREF+") (class "Default")
      (node (ref "R16") (pin "2") (pinfunction "2_2") (pintype "passive"))
      (node (ref "U2") (pin "21") (pinfunction "VREF+_21") (pintype "power_in"))
    )
    (net (code "113") (name "/VREF-") (class "Default")
      (node (ref "R18") (pin "2") (pinfunction "2_2") (pintype "passive"))
      (node (ref "U2") (pin "20") (pinfunction "VREF-_20") (pintype "power_in"))
    )
    (net (code "114") (name "/XI") (class "Default")
      (node (ref "C7") (pin "2") (pinfunction "2_2") (pintype "passive"))
      (node (ref "U2") (pin "12") (pinfunction "OSC_IN_12") (pintype "input"))
      (node (ref "Y1") (pin "1") (pinfunction "OSC1_1") (pintype "passive"))
    )
    (net (code "115") (name "/XO") (class "Default")
      (node (ref "C8") (pin "2") (pinfunction "2_2") (pintype "passive"))
      (node (ref "U2") (pin "13") (pinfunction "OSC_OUT_13") (pintype "output"))
      (node (ref "Y1") (pin "3") (pinfunction "OSC2_3") (pintype "passive"))
    )
    (net (code "116") (name "3V3") (class "Default")
      (node (ref "C2") (pin "2") (pinfunction "2_2") (pintype "passive"))
      (node (ref "C21") (pin "1") (pinfunction "1_1") (pintype "passive"))
      (node (ref "C4") (pin "2") (pinfunction "2_2") (pintype "passive"))
      (node (ref "C46") (pin "1") (pinfunction "1_1") (pintype "passive"))
      (node (ref "D2") (pin "1") (pinfunction "A_1") (pintype "passive"))
      (node (ref "D3") (pin "1") (pinfunction "A_1") (pintype "passive"))
      (node (ref "J2") (pin "7") (pinfunction "7_7") (pintype "passive"))
      (node (ref "J3") (pin "1") (pinfunction "1_1") (pintype "passive"))
      (node (ref "J3") (pin "12") (pinfunction "12_12") (pintype "passive"))
      (node (ref "J3") (pin "15") (pinfunction "15_15") (pintype "passive"))
      (node (ref "J3") (pin "16") (pinfunction "16_16") (pintype "passive"))
      (node (ref "J3") (pin "2") (pinfunction "2_2") (pintype "passive"))
      (node (ref "J3") (pin "3") (pinfunction "3_3") (pintype "passive"))
      (node (ref "J3") (pin "4") (pinfunction "4_4") (pintype "passive"))
      (node (ref "J5") (pin "2") (pinfunction "2_2") (pintype "passive"))
      (node (ref "J5") (pin "4") (pinfunction "4_4") (pintype "passive"))
      (node (ref "R1") (pin "2") (pinfunction "2_2") (pintype "passive"))
      (node (ref "R14") (pin "2") (pinfunction "2_2") (pintype "passive"))
      (node (ref "R2") (pin "1") (pinfunction "1_1") (pintype "passive"))
      (node (ref "R22") (pin "2") (pinfunction "2_2") (pintype "passive"))
      (node (ref "R24") (pin "2") (pinfunction "2_2") (pintype "passive"))
      (node (ref "R3") (pin "1") (pinfunction "1_1") (pintype "passive"))
      (node (ref "S3") (pin "3") (pinfunction "3_3") (pintype "passive"))
      (node (ref "U2") (pin "11") (pinfunction "VDD_5_11") (pintype "power_in"))
      (node (ref "U2") (pin "28") (pinfunction "VDD_4_28") (pintype "power_in"))
      (node (ref "U2") (pin "75") (pinfunction "VDD_2_75") (pintype "power_in"))
      (node (ref "U3") (pin "14") (pinfunction "VDD33/VIO_14") (pintype "power_in"))
    )
    (net (code "117") (name "5V_in") (class "Default")
      (node (ref "F2") (pin "1") (pinfunction "1_1") (pintype "passive"))
      (node (ref "P7") (pin "A4") (pinfunction "VBUS_A4") (pintype "bidirectional"))
      (node (ref "P7") (pin "B4") (pinfunction "VBUS_B4") (pintype "bidirectional"))
      (node (ref "P9") (pin "A4") (pinfunction "VBUS_A4") (pintype "bidirectional"))
      (node (ref "P9") (pin "B4") (pinfunction "VBUS_B4") (pintype "bidirectional"))
    )
    (net (code "118") (name "GND") (class "Default")
      (node (ref "C1") (pin "1") (pinfunction "1_1") (pintype "passive"))
      (node (ref "C10") (pin "1") (pinfunction "1_1") (pintype "passive"))
      (node (ref "C11") (pin "1") (pinfunction "1_1") (pintype "passive"))
      (node (ref "C12") (pin "2") (pinfunction "2_2") (pintype "passive"))
      (node (ref "C13") (pin "2") (pinfunction "2_2") (pintype "passive"))
      (node (ref "C2") (pin "1") (pinfunction "1_1") (pintype "passive"))
      (node (ref "C21") (pin "2") (pinfunction "2_2") (pintype "passive"))
      (node (ref "C3") (pin "2") (pinfunction "2_2") (pintype "passive"))
      (node (ref "C31") (pin "1") (pinfunction "1_1") (pintype "passive"))
      (node (ref "C32") (pin "1") (pinfunction "1_1") (pintype "passive"))
      (node (ref "C4") (pin "1") (pinfunction "1_1") (pintype "passive"))
      (node (ref "C46") (pin "2") (pinfunction "2_2") (pintype "passive"))
      (node (ref "C5") (pin "2") (pinfunction "2_2") (pintype "passive"))
      (node (ref "C6") (pin "2") (pinfunction "2_2") (pintype "passive"))
      (node (ref "C7") (pin "1") (pinfunction "1_1") (pintype "passive"))
      (node (ref "C8") (pin "1") (pinfunction "1_1") (pintype "passive"))
      (node (ref "C9") (pin "1") (pinfunction "1_1") (pintype "passive"))
      (node (ref "J2") (pin "5") (pinfunction "5_5") (pintype "passive"))
      (node (ref "J2") (pin "6") (pinfunction "6_6") (pintype "passive"))
      (node (ref "J3") (pin "20") (pinfunction "20_20") (pintype "passive"))
      (node (ref "J3") (pin "22") (pinfunction "22_22") (pintype "passive"))
      (node (ref "J3") (pin "25") (pinfunction "25_25") (pintype "passive"))
      (node (ref "J3") (pin "26") (pinfunction "26_26") (pintype "passive"))
      (node (ref "J3") (pin "7") (pinfunction "7_7") (pintype "passive"))
      (node (ref "J3") (pin "8") (pinfunction "8_8") (pintype "passive"))
      (node (ref "J3") (pin "9") (pinfunction "9_9") (pintype "passive"))
      (node (ref "J4") (pin "7") (pinfunction "7_7") (pintype "passive"))
      (node (ref "J5") (pin "6") (pinfunction "6_6") (pintype "passive"))
      (node (ref "J5") (pin "7") (pinfunction "7_7") (pintype "passive"))
      (node (ref "J7") (pin "4") (pinfunction "4_4") (pintype "passive"))
      (node (ref "P7") (pin "A1") (pinfunction "GND_A1") (pintype "bidirectional"))
      (node (ref "P7") (pin "B1") (pinfunction "GND_B1") (pintype "bidirectional"))
      (node (ref "P9") (pin "A1") (pinfunction "GND_A1") (pintype "bidirectional"))
      (node (ref "P9") (pin "B1") (pinfunction "GND_B1") (pintype "bidirectional"))
      (node (ref "PWR") (pin "2") (pinfunction "K_2") (pintype "passive"))
      (node (ref "R10") (pin "2") (pinfunction "2_2") (pintype "passive"))
      (node (ref "R11") (pin "2") (pinfunction "2_2") (pintype "passive"))
      (node (ref "R18") (pin "1") (pinfunction "1_1") (pintype "passive"))
      (node (ref "R21") (pin "1") (pinfunction "1_1") (pintype "passive"))
      (node (ref "R8") (pin "1") (pinfunction "1_1") (pintype "passive"))
      (node (ref "R9") (pin "1") (pinfunction "1_1") (pintype "passive"))
      (node (ref "S1") (pin "3") (pinfunction "B1_3") (pintype "passive"))
      (node (ref "S2") (pin "3") (pinfunction "B1_3") (pintype "passive"))
      (node (ref "S5") (pin "2") (pinfunction "2_2") (pintype "passive"))
      (node (ref "U1") (pin "1") (pinfunction "GND_1") (pintype "passive"))
      (node (ref "U2") (pin "10") (pinfunction "VSS_5_10") (pintype "power_in"))
      (node (ref "U2") (pin "19") (pinfunction "VSSA_19") (pintype "power_in"))
      (node (ref "U2") (pin "27") (pinfunction "VSS_4_27") (pintype "power_in"))
      (node (ref "U2") (pin "49") (pinfunction "VSS_1_49") (pintype "power_in"))
      (node (ref "U2") (pin "74") (pinfunction "VSS_2_74") (pintype "power_in"))
      (node (ref "U2") (pin "99") (pinfunction "VSS_3_99") (pintype "power_in"))
      (node (ref "U3") (pin "18") (pinfunction "VSS/GND_18") (pintype "power_in"))
    )
    (net (code "119") (name "Net-(D2-K)") (class "Default")
      (node (ref "D2") (pin "2") (pinfunction "K_2") (pintype "passive"))
      (node (ref "R13") (pin "2") (pinfunction "2_2") (pintype "passive"))
    )
    (net (code "120") (name "Net-(D3-K)") (class "Default")
      (node (ref "D3") (pin "2") (pinfunction "K_2") (pintype "passive"))
      (node (ref "R21") (pin "2") (pinfunction "2_2") (pintype "passive"))
    )
    (net (code "121") (name "Net-(J3-Pad6)") (class "Default")
      (node (ref "J3") (pin "6") (pinfunction "6_6") (pintype "passive"))
      (node (ref "R5") (pin "1") (pinfunction "1_1") (pintype "passive"))
    )
    (net (code "122") (name "Net-(J3-Pad10)") (class "Default")
      (node (ref "J3") (pin "10") (pinfunction "10_10") (pintype "passive"))
      (node (ref "J5") (pin "1") (pinfunction "1_1") (pintype "passive"))
    )
    (net (code "123") (name "Net-(LED1-A)") (class "Default")
      (node (ref "LED1") (pin "1") (pinfunction "A_1") (pintype "passive"))
      (node (ref "R2") (pin "2") (pinfunction "2_2") (pintype "passive"))
    )
    (net (code "124") (name "Net-(LED2-A)") (class "Default")
      (node (ref "LED2") (pin "1") (pinfunction "A_1") (pintype "passive"))
      (node (ref "R3") (pin "2") (pinfunction "2_2") (pintype "passive"))
    )
    (net (code "125") (name "Net-(P7-CC-PadA5)") (class "Default")
      (node (ref "P7") (pin "A5") (pinfunction "CC_A5") (pintype "bidirectional"))
      (node (ref "R8") (pin "2") (pinfunction "2_2") (pintype "passive"))
    )
    (net (code "126") (name "Net-(P7-CC-PadB5)") (class "Default")
      (node (ref "P7") (pin "B5") (pinfunction "CC_B5") (pintype "bidirectional"))
      (node (ref "R9") (pin "2") (pinfunction "2_2") (pintype "passive"))
    )
    (net (code "127") (name "Net-(P9-CC-PadA5)") (class "Default")
      (node (ref "P9") (pin "A5") (pinfunction "CC_A5") (pintype "bidirectional"))
      (node (ref "R10") (pin "1") (pinfunction "1_1") (pintype "passive"))
    )
    (net (code "128") (name "Net-(P9-CC-PadB5)") (class "Default")
      (node (ref "P9") (pin "B5") (pinfunction "CC_B5") (pintype "bidirectional"))
      (node (ref "R11") (pin "1") (pinfunction "1_1") (pintype "passive"))
    )
    (net (code "129") (name "Net-(PWR-A)") (class "Default")
      (node (ref "PWR") (pin "1") (pinfunction "A_1") (pintype "passive"))
      (node (ref "R1") (pin "1") (pinfunction "1_1") (pintype "passive"))
    )
    (net (code "130") (name "Net-(U1-VOUT)") (class "Default")
      (node (ref "C13") (pin "1") (pinfunction "1_1") (pintype "passive"))
      (node (ref "S3") (pin "1") (pinfunction "1_1") (pintype "passive"))
      (node (ref "U1") (pin "2") (pinfunction "VOUT_2") (pintype "passive"))
    )
    (net (code "131") (name "unconnected-(P7-RFU1-PadA8)") (class "Default")
      (node (ref "P7") (pin "A8") (pinfunction "RFU1_A8") (pintype "bidirectional+no_connect"))
    )
    (net (code "132") (name "unconnected-(P7-RFU1-PadB8)") (class "Default")
      (node (ref "P7") (pin "B8") (pinfunction "RFU1_B8") (pintype "bidirectional+no_connect"))
    )
    (net (code "133") (name "unconnected-(P9-RFU1-PadA8)") (class "Default")
      (node (ref "P9") (pin "A8") (pinfunction "RFU1_A8") (pintype "bidirectional+no_connect"))
    )
    (net (code "134") (name "unconnected-(P9-RFU1-PadB8)") (class "Default")
      (node (ref "P9") (pin "B8") (pinfunction "RFU1_B8") (pintype "bidirectional+no_connect"))
    )
    (net (code "135") (name "unconnected-(S1-A1-Pad4)") (class "Default")
      (node (ref "S1") (pin "4") (pinfunction "A1_4") (pintype "passive"))
    )
    (net (code "136") (name "unconnected-(S1-B0-Pad2)") (class "Default")
      (node (ref "S1") (pin "2") (pinfunction "B0_2") (pintype "passive"))
    )
    (net (code "137") (name "unconnected-(S2-A1-Pad4)") (class "Default")
      (node (ref "S2") (pin "4") (pinfunction "A1_4") (pintype "passive"))
    )
    (net (code "138") (name "unconnected-(S2-B0-Pad2)") (class "Default")
      (node (ref "S2") (pin "2") (pinfunction "B0_2") (pintype "passive"))
    )
    (net (code "139") (name "unconnected-(S3-Pad2)") (class "Default")
      (node (ref "S3") (pin "2") (pinfunction "2_2") (pintype "passive"))
    )
    (net (code "140") (name "unconnected-(U3-PA5{slash}UART1_CTS{slash}PA1_(no5V)-Pad2)") (class "Default")
      (node (ref "U3") (pin "2") (pinfunction "PA5/UART1_CTS/PA1_(no5V)_2") (pintype "bidirectional+no_connect"))
    )
    (net (code "141") (name "unconnected-(U3-PB12{slash}SPI2_NSS{slash}CAN2_RX-Pad5)") (class "Default")
      (node (ref "U3") (pin "5") (pinfunction "PB12/SPI2_NSS/CAN2_RX_5") (pintype "bidirectional+no_connect"))
    )
    (net (code "142") (name "unconnected-(U3-PB14{slash}SPI2_MISO{slash}UART3_RTS-Pad7)") (class "Default")
      (node (ref "U3") (pin "7") (pinfunction "PB14/SPI2_MISO/UART3_RTS_7") (pintype "bidirectional+no_connect"))
    )
    (net (code "143") (name "unconnected-(U3-PB15{slash}SPI2_MOSI{slash}UART1_TX-Pad8)") (class "Default")
      (node (ref "U3") (pin "8") (pinfunction "PB15/SPI2_MOSI/UART1_TX_8") (pintype "bidirectional+no_connect"))
    )
  )
)
